# UnderWaterMetalDetector_v2.net
KiCad netlist of a schematic drawn in EAGLE
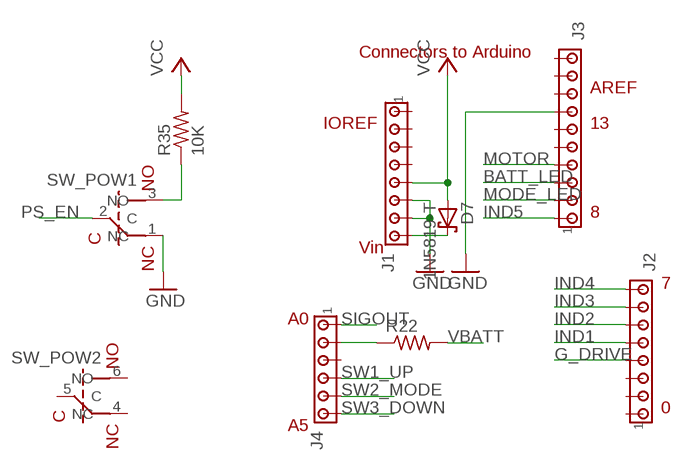
[diagram p0: schematic, sheet 1]
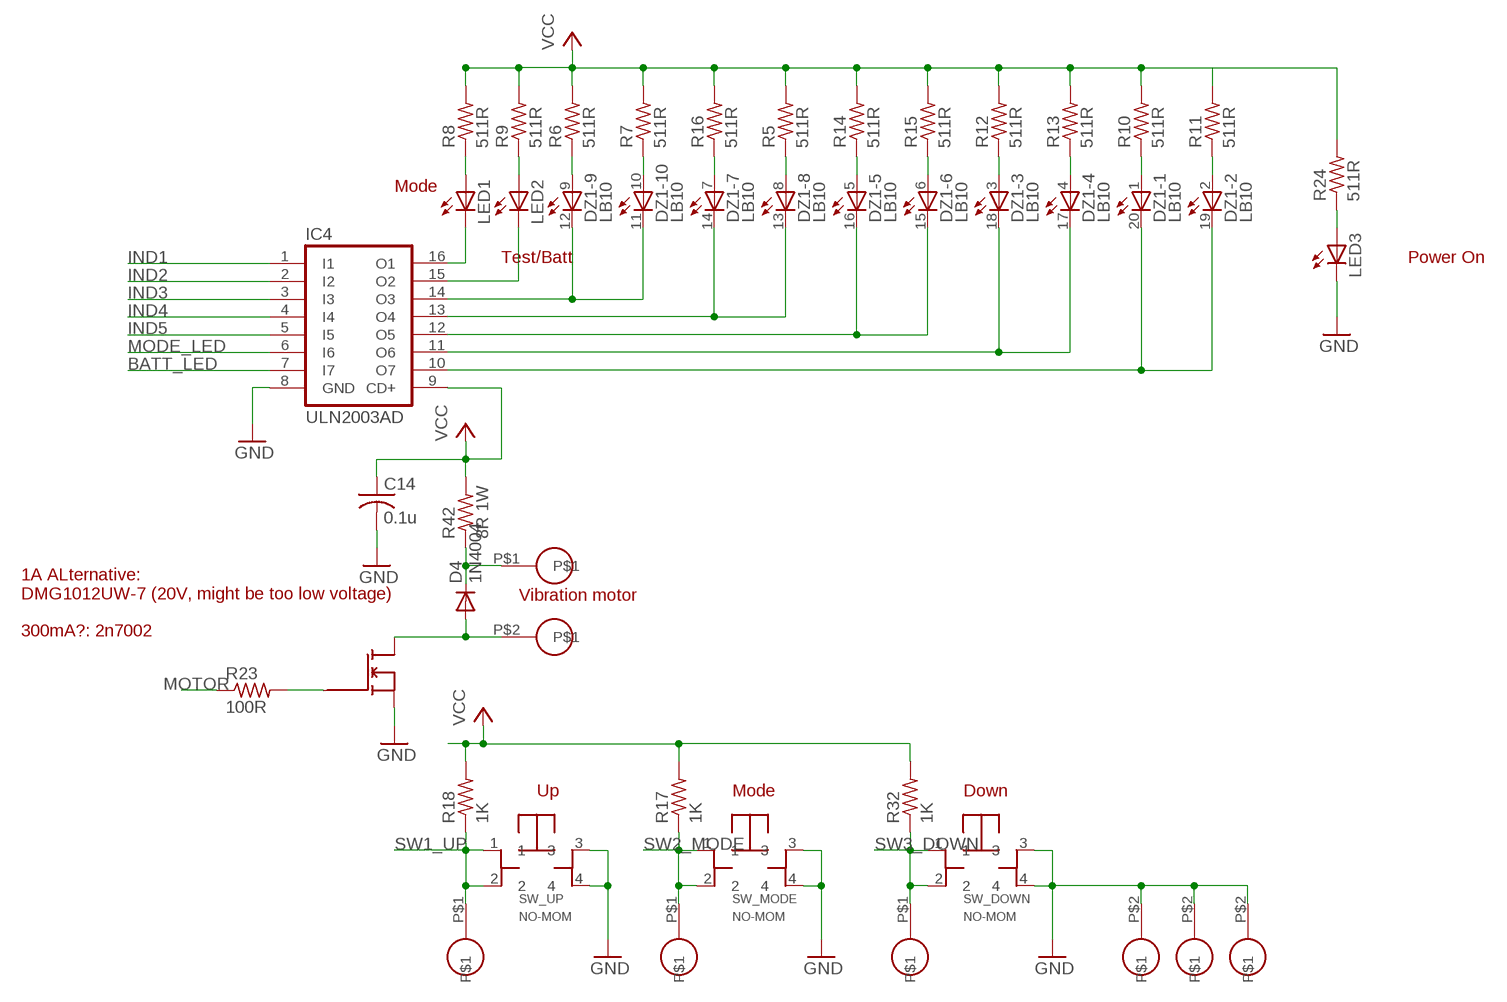
[diagram p1: schematic, sheet 2]
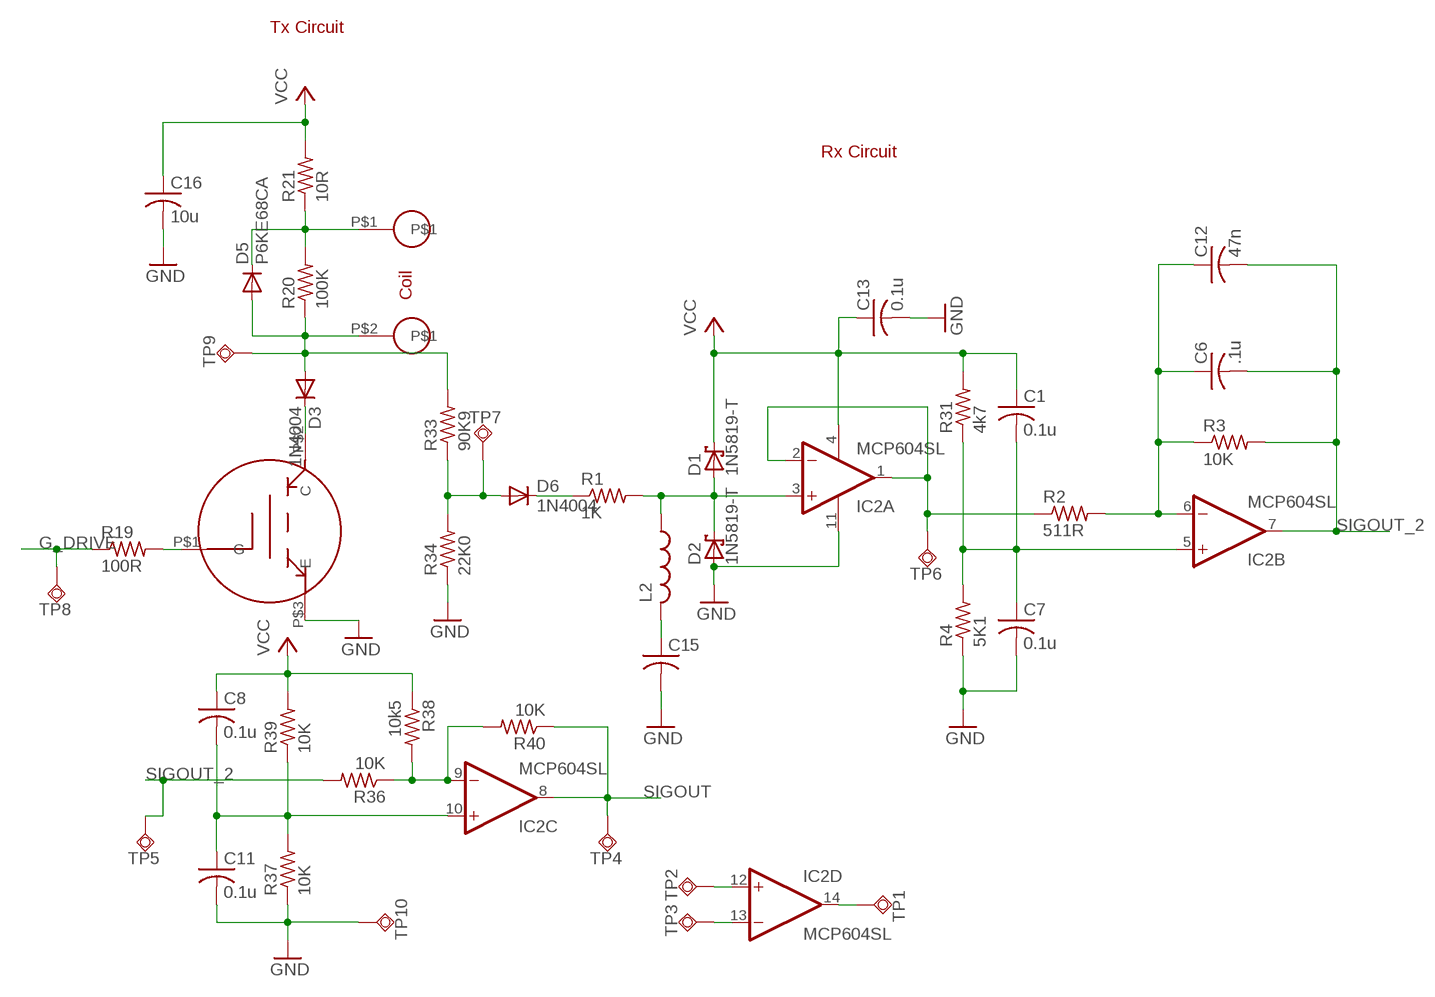
[diagram p2: schematic, sheet 3]
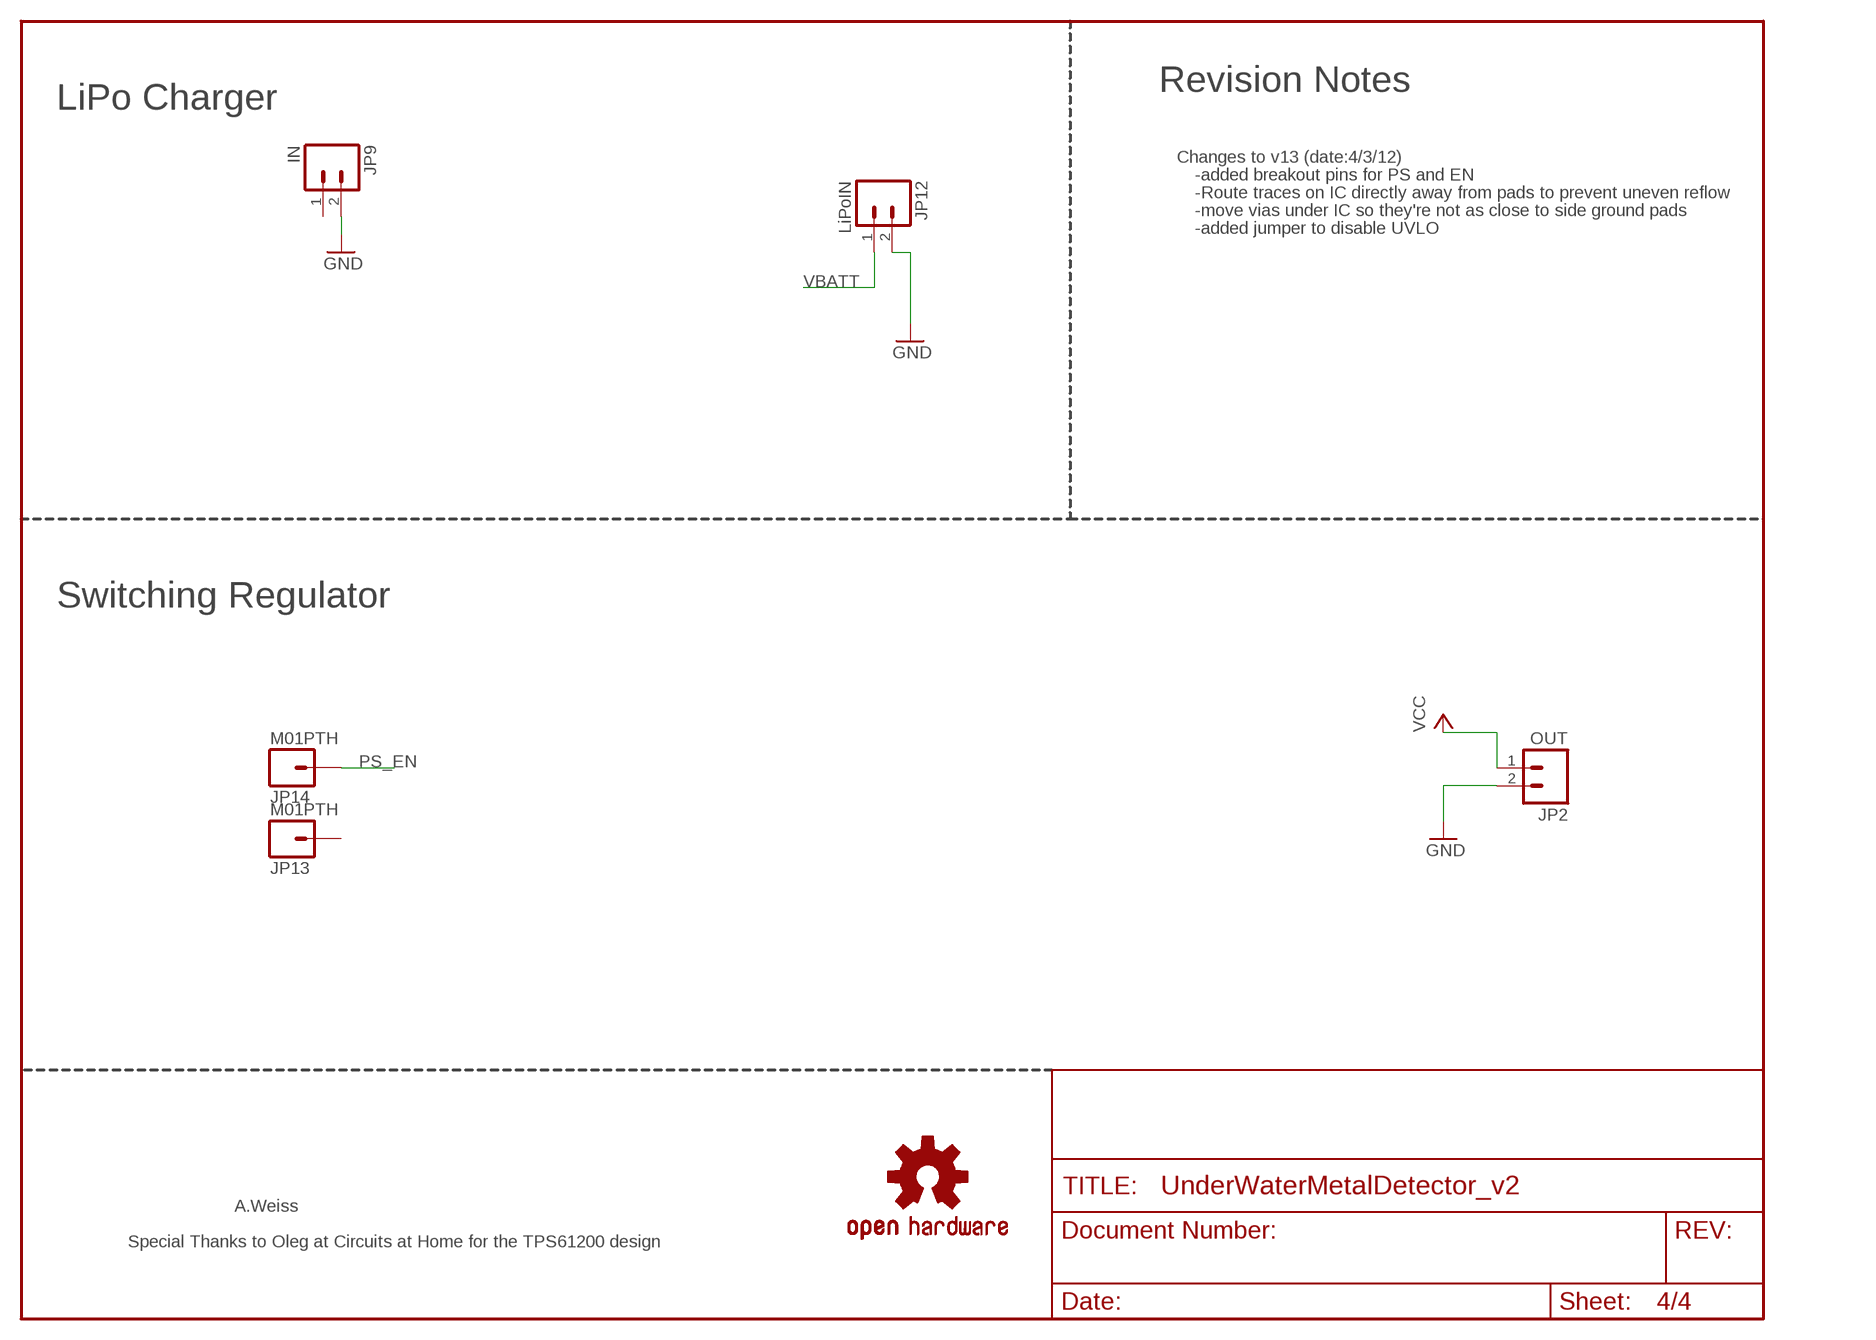
[diagram p3: schematic, sheet 4]

(export (version "E")
  (design (tool "Eeschema 10.0.6"))
  (components
    (comp (ref "C1")
      (value "0.1u")
      (footprint "eagle-import:C1206")
      (libsource (lib "eagle-import") (part "C-USC1206"))
    )
    (comp (ref "C6")
      (value ".1u")
      (footprint "eagle-import:C1206")
      (libsource (lib "eagle-import") (part "C-USC1206"))
    )
    (comp (ref "C7")
      (value "0.1u")
      (footprint "eagle-import:C1206")
      (libsource (lib "eagle-import") (part "C-USC1206"))
    )
    (comp (ref "C8")
      (value "0.1u")
      (footprint "eagle-import:C1206")
      (libsource (lib "eagle-import") (part "C-USC1206"))
    )
    (comp (ref "C11")
      (value "0.1u")
      (footprint "eagle-import:C1206")
      (libsource (lib "eagle-import") (part "C-USC1206"))
    )
    (comp (ref "C12")
      (value "47n")
      (footprint "eagle-import:C1206")
      (libsource (lib "eagle-import") (part "C-USC1206"))
    )
    (comp (ref "C13")
      (value "0.1u")
      (footprint "eagle-import:C1206")
      (libsource (lib "eagle-import") (part "C-USC1206"))
    )
    (comp (ref "C15")
      (value "C-USC1206")
      (footprint "eagle-import:C1206")
      (libsource (lib "eagle-import") (part "C-USC1206"))
    )
    (comp (ref "C16")
      (value "10u")
      (footprint "eagle-import:C1206")
      (libsource (lib "eagle-import") (part "C-USC1206"))
    )
    (comp (ref "COIL")
      (value "CON-SIP2-0.1")
      (footprint "eagle-import:CON-SIP2-0.1")
      (libsource (lib "eagle-import") (part "CON-SIP2-0.1"))
    )
    (comp (ref "D1")
      (value "1N5819-T")
      (footprint "eagle-import:DO41-7.6")
      (libsource (lib "eagle-import") (part "1N5819-T"))
    )
    (comp (ref "D2")
      (value "1N5819-T")
      (footprint "eagle-import:DO41-7.6")
      (libsource (lib "eagle-import") (part "1N5819-T"))
    )
    (comp (ref "D3")
      (value "1N4004")
      (footprint "eagle-import:DO41-10")
      (libsource (lib "eagle-import") (part "1N4004"))
    )
    (comp (ref "D5")
      (value "P6KE68CA")
      (footprint "eagle-import:D-5")
      (libsource (lib "eagle-import") (part "DIODE-D-5"))
    )
    (comp (ref "D6")
      (value "1N4004")
      (footprint "eagle-import:DO41-10")
      (libsource (lib "eagle-import") (part "1N4004"))
    )
    (comp (ref "IC2")
      (value "MCP604SL")
      (footprint "eagle-import:SO14")
      (libsource (lib "eagle-import") (part "MCP604SL"))
    )
    (comp (ref "L2")
      (value "L-US0204V")
      (footprint "eagle-import:0204V")
      (libsource (lib "eagle-import") (part "L-US0204V"))
    )
    (comp (ref "Q1")
      (value "STGP18N40LZ")
      (footprint "eagle-import:TO-220-HORIZ")
      (libsource (lib "eagle-import") (part "STGP18N40LZ"))
    )
    (comp (ref "R1")
      (value "1K")
      (footprint "eagle-import:M1206")
      (libsource (lib "eagle-import") (part "R-US_M1206"))
    )
    (comp (ref "R2")
      (value "511R")
      (footprint "eagle-import:R1206")
      (libsource (lib "eagle-import") (part "R-US_R1206"))
    )
    (comp (ref "R3")
      (value "10K")
      (footprint "eagle-import:R1206")
      (libsource (lib "eagle-import") (part "R-US_R1206"))
    )
    (comp (ref "R4")
      (value "5K1")
      (footprint "eagle-import:R1206")
      (libsource (lib "eagle-import") (part "R-US_R1206"))
    )
    (comp (ref "R19")
      (value "100R")
      (footprint "eagle-import:R1206")
      (libsource (lib "eagle-import") (part "R-US_R1206"))
    )
    (comp (ref "R20")
      (value "100K")
      (footprint "eagle-import:M1206")
      (libsource (lib "eagle-import") (part "R-US_M1206"))
    )
    (comp (ref "R21")
      (value "10R")
      (footprint "eagle-import:R2512")
      (libsource (lib "eagle-import") (part "R-US_R2512"))
    )
    (comp (ref "R31")
      (value "4k7")
      (footprint "eagle-import:R1206")
      (libsource (lib "eagle-import") (part "R-US_R1206"))
    )
    (comp (ref "R33")
      (value "90K9")
      (footprint "eagle-import:M1206")
      (libsource (lib "eagle-import") (part "R-US_M1206"))
    )
    (comp (ref "R34")
      (value "22K0")
      (footprint "eagle-import:M1206")
      (libsource (lib "eagle-import") (part "R-US_M1206"))
    )
    (comp (ref "R36")
      (value "10K")
      (footprint "eagle-import:M1206")
      (libsource (lib "eagle-import") (part "R-US_M1206"))
    )
    (comp (ref "R37")
      (value "10K")
      (footprint "eagle-import:M1206")
      (libsource (lib "eagle-import") (part "R-US_M1206"))
    )
    (comp (ref "R38")
      (value "10k5")
      (footprint "eagle-import:M1206")
      (libsource (lib "eagle-import") (part "R-US_M1206"))
    )
    (comp (ref "R39")
      (value "10K")
      (footprint "eagle-import:M1206")
      (libsource (lib "eagle-import") (part "R-US_M1206"))
    )
    (comp (ref "R40")
      (value "10K")
      (footprint "eagle-import:M1206")
      (libsource (lib "eagle-import") (part "R-US_M1206"))
    )
    (comp (ref "TP1")
      (value "TPSQPAD1-13")
      (footprint "eagle-import:P1-13")
      (libsource (lib "eagle-import") (part "TPSQPAD1-13"))
    )
    (comp (ref "TP2")
      (value "TPSQPAD1-13")
      (footprint "eagle-import:P1-13")
      (libsource (lib "eagle-import") (part "TPSQPAD1-13"))
    )
    (comp (ref "TP3")
      (value "TPSQPAD1-13")
      (footprint "eagle-import:P1-13")
      (libsource (lib "eagle-import") (part "TPSQPAD1-13"))
    )
    (comp (ref "TP4")
      (value "TPSQPAD1-13")
      (footprint "eagle-import:P1-13")
      (libsource (lib "eagle-import") (part "TPSQPAD1-13"))
    )
    (comp (ref "TP5")
      (value "TPSQPAD1-13")
      (footprint "eagle-import:P1-13")
      (libsource (lib "eagle-import") (part "TPSQPAD1-13"))
    )
    (comp (ref "TP6")
      (value "TPSQPAD1-13")
      (footprint "eagle-import:P1-13")
      (libsource (lib "eagle-import") (part "TPSQPAD1-13"))
    )
    (comp (ref "TP7")
      (value "TPSQPAD1-13")
      (footprint "eagle-import:P1-13")
      (libsource (lib "eagle-import") (part "TPSQPAD1-13"))
    )
    (comp (ref "TP8")
      (value "TPSQPAD1-13")
      (footprint "eagle-import:P1-13")
      (libsource (lib "eagle-import") (part "TPSQPAD1-13"))
    )
    (comp (ref "TP9")
      (value "TPSQPAD1-13")
      (footprint "eagle-import:P1-13")
      (libsource (lib "eagle-import") (part "TPSQPAD1-13"))
    )
    (comp (ref "TP10")
      (value "TPSQPAD1-13")
      (footprint "eagle-import:P1-13")
      (libsource (lib "eagle-import") (part "TPSQPAD1-13"))
    )
    (comp (ref "D7")
      (value "1N5819-T")
      (footprint "eagle-import:DO41-7.6")
      (libsource (lib "eagle-import") (part "1N5819-T"))
    )
    (comp (ref "J1")
      (value "MTA08-100")
      (footprint "eagle-import:10X08MTA")
      (libsource (lib "eagle-import") (part "MTA08-100"))
    )
    (comp (ref "J2")
      (value "MTA08-100")
      (footprint "eagle-import:10X08MTA")
      (libsource (lib "eagle-import") (part "MTA08-100"))
    )
    (comp (ref "J3")
      (value "MTA10-100")
      (footprint "eagle-import:10X10MTA")
      (libsource (lib "eagle-import") (part "MTA10-100"))
    )
    (comp (ref "J4")
      (value "MTA06-100")
      (footprint "eagle-import:10X06MTA")
      (libsource (lib "eagle-import") (part "MTA06-100"))
    )
    (comp (ref "R22")
      (value "R-US_R1206")
      (footprint "eagle-import:R1206")
      (libsource (lib "eagle-import") (part "R-US_R1206"))
    )
    (comp (ref "R35")
      (value "10K")
      (footprint "eagle-import:R1206")
      (libsource (lib "eagle-import") (part "R-US_R1206"))
    )
    (comp (ref "SW_POW")
      (value "SW-TL2201EEYA")
      (footprint "eagle-import:SW-TL2201EEYA")
      (libsource (lib "eagle-import") (part "SW-TL2201EEYA"))
    )
    (comp (ref "C14")
      (value "0.1u")
      (footprint "eagle-import:C1206")
      (libsource (lib "eagle-import") (part "C-USC1206"))
    )
    (comp (ref "D4")
      (value "1N4004")
      (footprint "eagle-import:DO41-10")
      (libsource (lib "eagle-import") (part "1N4004"))
    )
    (comp (ref "DOWN")
      (value "CON-SIP2-0.1")
      (footprint "eagle-import:CON-SIP2-0.1")
      (libsource (lib "eagle-import") (part "CON-SIP2-0.1"))
    )
    (comp (ref "DZ1")
      (value "LB10")
      (footprint "eagle-import:LB10")
      (libsource (lib "eagle-import") (part "LB10"))
    )
    (comp (ref "IC4")
      (value "ULN2003AD")
      (footprint "eagle-import:SO16")
      (libsource (lib "eagle-import") (part "ULN2003AD"))
    )
    (comp (ref "LED1")
      (value "LED5MM")
      (footprint "eagle-import:LED5MM")
      (libsource (lib "eagle-import") (part "LED5MM"))
    )
    (comp (ref "LED2")
      (value "LED5MM")
      (footprint "eagle-import:LED5MM")
      (libsource (lib "eagle-import") (part "LED5MM"))
    )
    (comp (ref "LED3")
      (value "LED5MM")
      (footprint "eagle-import:LED5MM")
      (libsource (lib "eagle-import") (part "LED5MM"))
    )
    (comp (ref "MODE")
      (value "CON-SIP2-0.1")
      (footprint "eagle-import:CON-SIP2-0.1")
      (libsource (lib "eagle-import") (part "CON-SIP2-0.1"))
    )
    (comp (ref "MOTOR")
      (value "CON-SIP2-0.1")
      (footprint "eagle-import:CON-SIP2-0.1")
      (libsource (lib "eagle-import") (part "CON-SIP2-0.1"))
    )
    (comp (ref "Q2")
      (value "FET-2N7000")
      (footprint "eagle-import:TO92")
      (libsource (lib "eagle-import") (part "FET-2N7000"))
    )
    (comp (ref "R5")
      (value "511R")
      (footprint "eagle-import:M1206")
      (libsource (lib "eagle-import") (part "R-US_M1206"))
    )
    (comp (ref "R6")
      (value "511R")
      (footprint "eagle-import:M1206")
      (libsource (lib "eagle-import") (part "R-US_M1206"))
    )
    (comp (ref "R7")
      (value "511R")
      (footprint "eagle-import:M1206")
      (libsource (lib "eagle-import") (part "R-US_M1206"))
    )
    (comp (ref "R8")
      (value "511R")
      (footprint "eagle-import:M1206")
      (libsource (lib "eagle-import") (part "R-US_M1206"))
    )
    (comp (ref "R9")
      (value "511R")
      (footprint "eagle-import:M1206")
      (libsource (lib "eagle-import") (part "R-US_M1206"))
    )
    (comp (ref "R10")
      (value "511R")
      (footprint "eagle-import:M1206")
      (libsource (lib "eagle-import") (part "R-US_M1206"))
    )
    (comp (ref "R11")
      (value "511R")
      (footprint "eagle-import:M1206")
      (libsource (lib "eagle-import") (part "R-US_M1206"))
    )
    (comp (ref "R12")
      (value "511R")
      (footprint "eagle-import:M1206")
      (libsource (lib "eagle-import") (part "R-US_M1206"))
    )
    (comp (ref "R13")
      (value "511R")
      (footprint "eagle-import:M1206")
      (libsource (lib "eagle-import") (part "R-US_M1206"))
    )
    (comp (ref "R14")
      (value "511R")
      (footprint "eagle-import:M1206")
      (libsource (lib "eagle-import") (part "R-US_M1206"))
    )
    (comp (ref "R15")
      (value "511R")
      (footprint "eagle-import:M1206")
      (libsource (lib "eagle-import") (part "R-US_M1206"))
    )
    (comp (ref "R16")
      (value "511R")
      (footprint "eagle-import:M1206")
      (libsource (lib "eagle-import") (part "R-US_M1206"))
    )
    (comp (ref "R17")
      (value "1K")
      (footprint "eagle-import:M1206")
      (libsource (lib "eagle-import") (part "R-US_M1206"))
    )
    (comp (ref "R18")
      (value "1K")
      (footprint "eagle-import:M1206")
      (libsource (lib "eagle-import") (part "R-US_M1206"))
    )
    (comp (ref "R23")
      (value "100R")
      (footprint "eagle-import:R1206")
      (libsource (lib "eagle-import") (part "R-US_R1206"))
    )
    (comp (ref "R24")
      (value "511R")
      (footprint "eagle-import:M1206")
      (libsource (lib "eagle-import") (part "R-US_M1206"))
    )
    (comp (ref "R32")
      (value "1K")
      (footprint "eagle-import:M1206")
      (libsource (lib "eagle-import") (part "R-US_M1206"))
    )
    (comp (ref "R42")
      (value "8R 1W")
      (footprint "eagle-import:R2512")
      (libsource (lib "eagle-import") (part "R-US_R2512"))
    )
    (comp (ref "SW_DOWN")
      (value "SW-SCHURTER-1301.9306")
      (footprint "eagle-import:SW-SCHURTER-1301.9306")
      (libsource (lib "eagle-import") (part "SW-SCHURTER-1301.9306"))
    )
    (comp (ref "SW_MODE")
      (value "SW-SCHURTER-1301.9306")
      (footprint "eagle-import:SW-SCHURTER-1301.9306")
      (libsource (lib "eagle-import") (part "SW-SCHURTER-1301.9306"))
    )
    (comp (ref "SW_UP")
      (value "SW-SCHURTER-1301.9306")
      (footprint "eagle-import:SW-SCHURTER-1301.9306")
      (libsource (lib "eagle-import") (part "SW-SCHURTER-1301.9306"))
    )
    (comp (ref "UP")
      (value "CON-SIP2-0.1")
      (footprint "eagle-import:CON-SIP2-0.1")
      (libsource (lib "eagle-import") (part "CON-SIP2-0.1"))
    )
    (comp (ref "JP2")
      (value "OUT")
      (footprint "eagle-import:1X02")
      (libsource (lib "eagle-import") (part "M02PTH"))
    )
    (comp (ref "JP9")
      (value "IN")
      (footprint "eagle-import:1X02")
      (libsource (lib "eagle-import") (part "M02PTH"))
    )
    (comp (ref "JP12")
      (value "LiPoIN")
      (footprint "eagle-import:1X02")
      (libsource (lib "eagle-import") (part "M02PTH"))
    )
    (comp (ref "JP13")
      (value "M01PTH")
      (footprint "eagle-import:1X01")
      (libsource (lib "eagle-import") (part "M01PTH"))
    )
    (comp (ref "JP14")
      (value "M01PTH")
      (footprint "eagle-import:1X01")
      (libsource (lib "eagle-import") (part "M01PTH"))
    )
    (comp (ref "U$3")
      (value "OSHW-LOGOS")
      (footprint "eagle-import:OSHW-LOGO-S")
      (libsource (lib "eagle-import") (part "OSHW-LOGOS"))
    )
  )
  (nets
    (net (code "1") (name "BATT_LED") (class "Default")
      (node (ref "IC4") (pin "7") (pinfunction "I7_7") (pintype "input"))
      (node (ref "J3") (pin "3") (pinfunction "3_3") (pintype "passive"))
    )
    (net (code "2") (name "GND") (class "Default")
      (node (ref "C11") (pin "2") (pinfunction "2_2") (pintype "passive"))
      (node (ref "C13") (pin "2") (pinfunction "2_2") (pintype "passive"))
      (node (ref "C14") (pin "2") (pinfunction "2_2") (pintype "passive"))
      (node (ref "C15") (pin "2") (pinfunction "2_2") (pintype "passive"))
      (node (ref "C16") (pin "2") (pinfunction "2_2") (pintype "passive"))
      (node (ref "C7") (pin "2") (pinfunction "2_2") (pintype "passive"))
      (node (ref "D2") (pin "A") (pinfunction "A_A") (pintype "passive"))
      (node (ref "DOWN") (pin "P$2") (pinfunction "P$1_P$2") (pintype "bidirectional"))
      (node (ref "IC2") (pin "11") (pinfunction "V-_11") (pintype "power_in"))
      (node (ref "IC4") (pin "8") (pinfunction "GND_8") (pintype "power_in"))
      (node (ref "J1") (pin "6") (pinfunction "6_6") (pintype "passive"))
      (node (ref "J1") (pin "7") (pinfunction "7_7") (pintype "passive"))
      (node (ref "J3") (pin "7") (pinfunction "7_7") (pintype "passive"))
      (node (ref "JP12") (pin "2") (pinfunction "2_2") (pintype "passive"))
      (node (ref "JP2") (pin "2") (pinfunction "2_2") (pintype "passive"))
      (node (ref "JP9") (pin "2") (pinfunction "2_2") (pintype "passive"))
      (node (ref "LED3") (pin "K") (pinfunction "C_K") (pintype "passive"))
      (node (ref "MODE") (pin "P$2") (pinfunction "P$1_P$2") (pintype "bidirectional"))
      (node (ref "Q1") (pin "P$3") (pinfunction "E_P$3") (pintype "bidirectional"))
      (node (ref "Q2") (pin "1") (pinfunction "S_1") (pintype "bidirectional"))
      (node (ref "R34") (pin "1") (pinfunction "1_1") (pintype "passive"))
      (node (ref "R37") (pin "1") (pinfunction "1_1") (pintype "passive"))
      (node (ref "R4") (pin "1") (pinfunction "1_1") (pintype "passive"))
      (node (ref "SW_DOWN") (pin "3") (pinfunction "3_3") (pintype "bidirectional"))
      (node (ref "SW_DOWN") (pin "4") (pinfunction "4_4") (pintype "bidirectional"))
      (node (ref "SW_MODE") (pin "3") (pinfunction "3_3") (pintype "bidirectional"))
      (node (ref "SW_MODE") (pin "4") (pinfunction "4_4") (pintype "bidirectional"))
      (node (ref "SW_POW") (pin "1") (pinfunction "NC_1") (pintype "bidirectional"))
      (node (ref "SW_UP") (pin "3") (pinfunction "3_3") (pintype "bidirectional"))
      (node (ref "SW_UP") (pin "4") (pinfunction "4_4") (pintype "bidirectional"))
      (node (ref "TP10") (pin "TP") (pinfunction "TP_TP") (pintype "input"))
      (node (ref "UP") (pin "P$2") (pinfunction "P$1_P$2") (pintype "bidirectional"))
    )
    (net (code "3") (name "G_DRIVE") (class "Default")
      (node (ref "J2") (pin "4") (pinfunction "4_4") (pintype "passive"))
      (node (ref "R19") (pin "1") (pinfunction "1_1") (pintype "passive"))
      (node (ref "TP8") (pin "TP") (pinfunction "TP_TP") (pintype "input"))
    )
    (net (code "4") (name "IND1") (class "Default")
      (node (ref "IC4") (pin "1") (pinfunction "I1_1") (pintype "input"))
      (node (ref "J2") (pin "5") (pinfunction "5_5") (pintype "passive"))
    )
    (net (code "5") (name "IND2") (class "Default")
      (node (ref "IC4") (pin "2") (pinfunction "I2_2") (pintype "input"))
      (node (ref "J2") (pin "6") (pinfunction "6_6") (pintype "passive"))
    )
    (net (code "6") (name "IND3") (class "Default")
      (node (ref "IC4") (pin "3") (pinfunction "I3_3") (pintype "input"))
      (node (ref "J2") (pin "7") (pinfunction "7_7") (pintype "passive"))
    )
    (net (code "7") (name "IND4") (class "Default")
      (node (ref "IC4") (pin "4") (pinfunction "I4_4") (pintype "input"))
      (node (ref "J2") (pin "8") (pinfunction "8_8") (pintype "passive"))
    )
    (net (code "8") (name "IND5") (class "Default")
      (node (ref "IC4") (pin "5") (pinfunction "I5_5") (pintype "input"))
      (node (ref "J3") (pin "1") (pinfunction "1_1") (pintype "passive"))
    )
    (net (code "9") (name "MODE_LED") (class "Default")
      (node (ref "IC4") (pin "6") (pinfunction "I6_6") (pintype "input"))
      (node (ref "J3") (pin "2") (pinfunction "2_2") (pintype "passive"))
    )
    (net (code "10") (name "MOTOR") (class "Default")
      (node (ref "J3") (pin "4") (pinfunction "4_4") (pintype "passive"))
      (node (ref "R23") (pin "1") (pinfunction "1_1") (pintype "passive"))
    )
    (net (code "11") (name "Net-(C15-Pad1)") (class "Default")
      (node (ref "C15") (pin "1") (pinfunction "1_1") (pintype "passive"))
      (node (ref "L2") (pin "2") (pinfunction "2_2") (pintype "passive"))
    )
    (net (code "12") (name "Net-(COIL-PadP$1)") (class "Default")
      (node (ref "COIL") (pin "P$1") (pinfunction "P$1_P$1") (pintype "bidirectional"))
      (node (ref "D5") (pin "C") (pinfunction "C_C") (pintype "passive"))
      (node (ref "R20") (pin "2") (pinfunction "2_2") (pintype "passive"))
      (node (ref "R21") (pin "1") (pinfunction "1_1") (pintype "passive"))
    )
    (net (code "13") (name "Net-(COILB-P$1)") (class "Default")
      (node (ref "COIL") (pin "P$2") (pinfunction "P$1_P$2") (pintype "bidirectional"))
      (node (ref "D3") (pin "A") (pinfunction "A_A") (pintype "passive"))
      (node (ref "D5") (pin "A") (pinfunction "A_A") (pintype "passive"))
      (node (ref "R20") (pin "1") (pinfunction "1_1") (pintype "passive"))
      (node (ref "R33") (pin "2") (pinfunction "2_2") (pintype "passive"))
      (node (ref "TP9") (pin "TP") (pinfunction "TP_TP") (pintype "input"))
    )
    (net (code "14") (name "Net-(D4-PadC)") (class "Default")
      (node (ref "D4") (pin "C") (pinfunction "C_C") (pintype "passive"))
      (node (ref "MOTOR") (pin "P$1") (pinfunction "P$1_P$1") (pintype "bidirectional"))
      (node (ref "R42") (pin "1") (pinfunction "1_1") (pintype "passive"))
    )
    (net (code "15") (name "Net-(D6-PadA)") (class "Default")
      (node (ref "D6") (pin "A") (pinfunction "A_A") (pintype "passive"))
      (node (ref "R33") (pin "1") (pinfunction "1_1") (pintype "passive"))
      (node (ref "R34") (pin "2") (pinfunction "2_2") (pintype "passive"))
      (node (ref "TP7") (pin "TP") (pinfunction "TP_TP") (pintype "input"))
    )
    (net (code "16") (name "Net-(D6-PadC)") (class "Default")
      (node (ref "D6") (pin "C") (pinfunction "C_C") (pintype "passive"))
      (node (ref "R1") (pin "1") (pinfunction "1_1") (pintype "passive"))
    )
    (net (code "17") (name "Net-(D7-PadC)") (class "Default")
      (node (ref "D7") (pin "C") (pinfunction "C_C") (pintype "passive"))
      (node (ref "J1") (pin "8") (pinfunction "8_8") (pintype "passive"))
    )
    (net (code "18") (name "Net-(DZ1A-A)") (class "Default")
      (node (ref "DZ1") (pin "1") (pinfunction "A_1") (pintype "passive"))
      (node (ref "R10") (pin "1") (pinfunction "1_1") (pintype "passive"))
    )
    (net (code "19") (name "Net-(DZ1A-C)") (class "Default")
      (node (ref "DZ1") (pin "19") (pinfunction "C_19") (pintype "passive"))
      (node (ref "DZ1") (pin "20") (pinfunction "C_20") (pintype "passive"))
      (node (ref "IC4") (pin "10") (pinfunction "O7_10") (pintype "open_collector"))
    )
    (net (code "20") (name "Net-(DZ1B-A)") (class "Default")
      (node (ref "DZ1") (pin "10") (pinfunction "A_10") (pintype "passive"))
      (node (ref "R7") (pin "1") (pinfunction "1_1") (pintype "passive"))
    )
    (net (code "21") (name "Net-(DZ1B-C)") (class "Default")
      (node (ref "DZ1") (pin "11") (pinfunction "C_11") (pintype "passive"))
      (node (ref "DZ1") (pin "12") (pinfunction "C_12") (pintype "passive"))
      (node (ref "IC4") (pin "14") (pinfunction "O3_14") (pintype "open_collector"))
    )
    (net (code "22") (name "Net-(DZ1C-A)") (class "Default")
      (node (ref "DZ1") (pin "2") (pinfunction "A_2") (pintype "passive"))
      (node (ref "R11") (pin "1") (pinfunction "1_1") (pintype "passive"))
    )
    (net (code "23") (name "Net-(DZ1D-A)") (class "Default")
      (node (ref "DZ1") (pin "3") (pinfunction "A_3") (pintype "passive"))
      (node (ref "R12") (pin "1") (pinfunction "1_1") (pintype "passive"))
    )
    (net (code "24") (name "Net-(DZ1D-C)") (class "Default")
      (node (ref "DZ1") (pin "17") (pinfunction "C_17") (pintype "passive"))
      (node (ref "DZ1") (pin "18") (pinfunction "C_18") (pintype "passive"))
      (node (ref "IC4") (pin "11") (pinfunction "O6_11") (pintype "open_collector"))
    )
    (net (code "25") (name "Net-(DZ1E-A)") (class "Default")
      (node (ref "DZ1") (pin "4") (pinfunction "A_4") (pintype "passive"))
      (node (ref "R13") (pin "1") (pinfunction "1_1") (pintype "passive"))
    )
    (net (code "26") (name "Net-(DZ1F-A)") (class "Default")
      (node (ref "DZ1") (pin "5") (pinfunction "A_5") (pintype "passive"))
      (node (ref "R14") (pin "1") (pinfunction "1_1") (pintype "passive"))
    )
    (net (code "27") (name "Net-(DZ1F-C)") (class "Default")
      (node (ref "DZ1") (pin "15") (pinfunction "C_15") (pintype "passive"))
      (node (ref "DZ1") (pin "16") (pinfunction "C_16") (pintype "passive"))
      (node (ref "IC4") (pin "12") (pinfunction "O5_12") (pintype "open_collector"))
    )
    (net (code "28") (name "Net-(DZ1G-A)") (class "Default")
      (node (ref "DZ1") (pin "6") (pinfunction "A_6") (pintype "passive"))
      (node (ref "R15") (pin "1") (pinfunction "1_1") (pintype "passive"))
    )
    (net (code "29") (name "Net-(DZ1H-A)") (class "Default")
      (node (ref "DZ1") (pin "7") (pinfunction "A_7") (pintype "passive"))
      (node (ref "R16") (pin "1") (pinfunction "1_1") (pintype "passive"))
    )
    (net (code "30") (name "Net-(DZ1H-C)") (class "Default")
      (node (ref "DZ1") (pin "13") (pinfunction "C_13") (pintype "passive"))
      (node (ref "DZ1") (pin "14") (pinfunction "C_14") (pintype "passive"))
      (node (ref "IC4") (pin "13") (pinfunction "O4_13") (pintype "open_collector"))
    )
    (net (code "31") (name "Net-(DZ1I-A)") (class "Default")
      (node (ref "DZ1") (pin "8") (pinfunction "A_8") (pintype "passive"))
      (node (ref "R5") (pin "1") (pinfunction "1_1") (pintype "passive"))
    )
    (net (code "32") (name "Net-(DZ1J-A)") (class "Default")
      (node (ref "DZ1") (pin "9") (pinfunction "A_9") (pintype "passive"))
      (node (ref "R6") (pin "1") (pinfunction "1_1") (pintype "passive"))
    )
    (net (code "33") (name "Net-(IC2A-+IN)") (class "Default")
      (node (ref "D1") (pin "A") (pinfunction "A_A") (pintype "passive"))
      (node (ref "D2") (pin "C") (pinfunction "C_C") (pintype "passive"))
      (node (ref "IC2") (pin "3") (pinfunction "+IN_3") (pintype "input"))
      (node (ref "L2") (pin "1") (pinfunction "1_1") (pintype "passive"))
      (node (ref "R1") (pin "2") (pinfunction "2_2") (pintype "passive"))
    )
    (net (code "34") (name "Net-(IC2A--IN)") (class "Default")
      (node (ref "IC2") (pin "1") (pinfunction "OUT_1") (pintype "output"))
      (node (ref "IC2") (pin "2") (pinfunction "-IN_2") (pintype "input"))
      (node (ref "R2") (pin "1") (pinfunction "1_1") (pintype "passive"))
      (node (ref "TP6") (pin "TP") (pinfunction "TP_TP") (pintype "input"))
    )
    (net (code "35") (name "Net-(IC2B-+IN)") (class "Default")
      (node (ref "C1") (pin "2") (pinfunction "2_2") (pintype "passive"))
      (node (ref "C7") (pin "1") (pinfunction "1_1") (pintype "passive"))
      (node (ref "IC2") (pin "5") (pinfunction "+IN_5") (pintype "input"))
      (node (ref "R31") (pin "1") (pinfunction "1_1") (pintype "passive"))
      (node (ref "R4") (pin "2") (pinfunction "2_2") (pintype "passive"))
    )
    (net (code "36") (name "Net-(IC2B--IN)") (class "Default")
      (node (ref "C12") (pin "1") (pinfunction "1_1") (pintype "passive"))
      (node (ref "C6") (pin "1") (pinfunction "1_1") (pintype "passive"))
      (node (ref "IC2") (pin "6") (pinfunction "-IN_6") (pintype "input"))
      (node (ref "R2") (pin "2") (pinfunction "2_2") (pintype "passive"))
      (node (ref "R3") (pin "1") (pinfunction "1_1") (pintype "passive"))
    )
    (net (code "37") (name "Net-(IC2C-+IN)") (class "Default")
      (node (ref "C11") (pin "1") (pinfunction "1_1") (pintype "passive"))
      (node (ref "C8") (pin "2") (pinfunction "2_2") (pintype "passive"))
      (node (ref "IC2") (pin "10") (pinfunction "+IN_10") (pintype "input"))
      (node (ref "R37") (pin "2") (pinfunction "2_2") (pintype "passive"))
      (node (ref "R39") (pin "1") (pinfunction "1_1") (pintype "passive"))
    )
    (net (code "38") (name "Net-(IC2C--IN)") (class "Default")
      (node (ref "IC2") (pin "9") (pinfunction "-IN_9") (pintype "input"))
      (node (ref "R36") (pin "1") (pinfunction "1_1") (pintype "passive"))
      (node (ref "R38") (pin "2") (pinfunction "2_2") (pintype "passive"))
      (node (ref "R40") (pin "2") (pinfunction "2_2") (pintype "passive"))
    )
    (net (code "39") (name "Net-(IC2D-+IN)") (class "Default")
      (node (ref "IC2") (pin "12") (pinfunction "+IN_12") (pintype "input"))
      (node (ref "TP2") (pin "TP") (pinfunction "TP_TP") (pintype "input"))
    )
    (net (code "40") (name "Net-(IC2D--IN)") (class "Default")
      (node (ref "IC2") (pin "13") (pinfunction "-IN_13") (pintype "input"))
      (node (ref "TP3") (pin "TP") (pinfunction "TP_TP") (pintype "input"))
    )
    (net (code "41") (name "Net-(IC2D-OUT)") (class "Default")
      (node (ref "IC2") (pin "14") (pinfunction "OUT_14") (pintype "output"))
      (node (ref "TP1") (pin "TP") (pinfunction "TP_TP") (pintype "input"))
    )
    (net (code "42") (name "Net-(IC4-O1)") (class "Default")
      (node (ref "IC4") (pin "16") (pinfunction "O1_16") (pintype "open_collector"))
      (node (ref "LED1") (pin "K") (pinfunction "C_K") (pintype "passive"))
    )
    (net (code "43") (name "Net-(IC4-O2)") (class "Default")
      (node (ref "IC4") (pin "15") (pinfunction "O2_15") (pintype "open_collector"))
      (node (ref "LED2") (pin "K") (pinfunction "C_K") (pintype "passive"))
    )
    (net (code "44") (name "Net-(J4-2)") (class "Default")
      (node (ref "J4") (pin "5") (pinfunction "2_5") (pintype "passive"))
      (node (ref "R22") (pin "1") (pinfunction "1_1") (pintype "passive"))
    )
    (net (code "45") (name "Net-(LED1-PadA)") (class "Default")
      (node (ref "LED1") (pin "A") (pinfunction "A_A") (pintype "passive"))
      (node (ref "R8") (pin "1") (pinfunction "1_1") (pintype "passive"))
    )
    (net (code "46") (name "Net-(LED2-PadA)") (class "Default")
      (node (ref "LED2") (pin "A") (pinfunction "A_A") (pintype "passive"))
      (node (ref "R9") (pin "1") (pinfunction "1_1") (pintype "passive"))
    )
    (net (code "47") (name "Net-(LED3-PadA)") (class "Default")
      (node (ref "LED3") (pin "A") (pinfunction "A_A") (pintype "passive"))
      (node (ref "R24") (pin "1") (pinfunction "1_1") (pintype "passive"))
    )
    (net (code "48") (name "Net-(MOTORB-P$1)") (class "Default")
      (node (ref "D4") (pin "A") (pinfunction "A_A") (pintype "passive"))
      (node (ref "MOTOR") (pin "P$2") (pinfunction "P$1_P$2") (pintype "bidirectional"))
      (node (ref "Q2") (pin "3") (pinfunction "D_3") (pintype "bidirectional"))
    )
    (net (code "49") (name "Net-(Q1-C)") (class "Default")
      (node (ref "D3") (pin "C") (pinfunction "C_C") (pintype "passive"))
      (node (ref "Q1") (pin "P$2") (pinfunction "C_P$2") (pintype "bidirectional"))
    )
    (net (code "50") (name "Net-(Q1-G)") (class "Default")
      (node (ref "Q1") (pin "P$1") (pinfunction "G_P$1") (pintype "bidirectional"))
      (node (ref "R19") (pin "2") (pinfunction "2_2") (pintype "passive"))
    )
    (net (code "51") (name "Net-(Q2-G)") (class "Default")
      (node (ref "Q2") (pin "2") (pinfunction "G_2") (pintype "bidirectional"))
      (node (ref "R23") (pin "2") (pinfunction "2_2") (pintype "passive"))
    )
    (net (code "52") (name "Net-(SW_POWA-NO)") (class "Default")
      (node (ref "R35") (pin "1") (pinfunction "1_1") (pintype "passive"))
      (node (ref "SW_POW") (pin "3") (pinfunction "NO_3") (pintype "bidirectional"))
    )
    (net (code "53") (name "PS_EN") (class "Default")
      (node (ref "JP14") (pin "1") (pinfunction "1_1") (pintype "passive"))
      (node (ref "SW_POW") (pin "2") (pinfunction "C_2") (pintype "bidirectional"))
    )
    (net (code "54") (name "SIGOUT") (class "Default")
      (node (ref "IC2") (pin "8") (pinfunction "OUT_8") (pintype "output"))
      (node (ref "J4") (pin "6") (pinfunction "1_6") (pintype "passive"))
      (node (ref "R40") (pin "1") (pinfunction "1_1") (pintype "passive"))
      (node (ref "TP4") (pin "TP") (pinfunction "TP_TP") (pintype "input"))
    )
    (net (code "55") (name "SIGOUT_2") (class "Default")
      (node (ref "C12") (pin "2") (pinfunction "2_2") (pintype "passive"))
      (node (ref "C6") (pin "2") (pinfunction "2_2") (pintype "passive"))
      (node (ref "IC2") (pin "7") (pinfunction "OUT_7") (pintype "output"))
      (node (ref "R3") (pin "2") (pinfunction "2_2") (pintype "passive"))
      (node (ref "R36") (pin "2") (pinfunction "2_2") (pintype "passive"))
      (node (ref "TP5") (pin "TP") (pinfunction "TP_TP") (pintype "input"))
    )
    (net (code "56") (name "SW1_UP") (class "Default")
      (node (ref "J4") (pin "3") (pinfunction "4_3") (pintype "passive"))
      (node (ref "R18") (pin "1") (pinfunction "1_1") (pintype "passive"))
      (node (ref "SW_UP") (pin "1") (pinfunction "1_1") (pintype "bidirectional"))
      (node (ref "SW_UP") (pin "2") (pinfunction "2_2") (pintype "bidirectional"))
      (node (ref "UP") (pin "P$1") (pinfunction "P$1_P$1") (pintype "bidirectional"))
    )
    (net (code "57") (name "SW2_MODE") (class "Default")
      (node (ref "J4") (pin "2") (pinfunction "5_2") (pintype "passive"))
      (node (ref "MODE") (pin "P$1") (pinfunction "P$1_P$1") (pintype "bidirectional"))
      (node (ref "R17") (pin "1") (pinfunction "1_1") (pintype "passive"))
      (node (ref "SW_MODE") (pin "1") (pinfunction "1_1") (pintype "bidirectional"))
      (node (ref "SW_MODE") (pin "2") (pinfunction "2_2") (pintype "bidirectional"))
    )
    (net (code "58") (name "SW3_DOWN") (class "Default")
      (node (ref "DOWN") (pin "P$1") (pinfunction "P$1_P$1") (pintype "bidirectional"))
      (node (ref "J4") (pin "1") (pinfunction "6_1") (pintype "passive"))
      (node (ref "R32") (pin "1") (pinfunction "1_1") (pintype "passive"))
      (node (ref "SW_DOWN") (pin "1") (pinfunction "1_1") (pintype "bidirectional"))
      (node (ref "SW_DOWN") (pin "2") (pinfunction "2_2") (pintype "bidirectional"))
    )
    (net (code "59") (name "VBATT") (class "Default")
      (node (ref "JP12") (pin "1") (pinfunction "1_1") (pintype "passive"))
      (node (ref "R22") (pin "2") (pinfunction "2_2") (pintype "passive"))
    )
    (net (code "60") (name "VCC") (class "Default")
      (node (ref "C1") (pin "1") (pinfunction "1_1") (pintype "passive"))
      (node (ref "C13") (pin "1") (pinfunction "1_1") (pintype "passive"))
      (node (ref "C14") (pin "1") (pinfunction "1_1") (pintype "passive"))
      (node (ref "C16") (pin "1") (pinfunction "1_1") (pintype "passive"))
      (node (ref "C8") (pin "1") (pinfunction "1_1") (pintype "passive"))
      (node (ref "D1") (pin "C") (pinfunction "C_C") (pintype "passive"))
      (node (ref "D7") (pin "A") (pinfunction "A_A") (pintype "passive"))
      (node (ref "IC2") (pin "4") (pinfunction "V+_4") (pintype "power_in"))
      (node (ref "IC4") (pin "9") (pinfunction "CD+_9") (pintype "passive"))
      (node (ref "J1") (pin "5") (pinfunction "5_5") (pintype "passive"))
      (node (ref "JP2") (pin "1") (pinfunction "1_1") (pintype "passive"))
      (node (ref "R10") (pin "2") (pinfunction "2_2") (pintype "passive"))
      (node (ref "R11") (pin "2") (pinfunction "2_2") (pintype "passive"))
      (node (ref "R12") (pin "2") (pinfunction "2_2") (pintype "passive"))
      (node (ref "R13") (pin "2") (pinfunction "2_2") (pintype "passive"))
      (node (ref "R14") (pin "2") (pinfunction "2_2") (pintype "passive"))
      (node (ref "R15") (pin "2") (pinfunction "2_2") (pintype "passive"))
      (node (ref "R16") (pin "2") (pinfunction "2_2") (pintype "passive"))
      (node (ref "R17") (pin "2") (pinfunction "2_2") (pintype "passive"))
      (node (ref "R18") (pin "2") (pinfunction "2_2") (pintype "passive"))
      (node (ref "R21") (pin "2") (pinfunction "2_2") (pintype "passive"))
      (node (ref "R24") (pin "2") (pinfunction "2_2") (pintype "passive"))
      (node (ref "R31") (pin "2") (pinfunction "2_2") (pintype "passive"))
      (node (ref "R32") (pin "2") (pinfunction "2_2") (pintype "passive"))
      (node (ref "R35") (pin "2") (pinfunction "2_2") (pintype "passive"))
      (node (ref "R38") (pin "1") (pinfunction "1_1") (pintype "passive"))
      (node (ref "R39") (pin "2") (pinfunction "2_2") (pintype "passive"))
      (node (ref "R42") (pin "2") (pinfunction "2_2") (pintype "passive"))
      (node (ref "R5") (pin "2") (pinfunction "2_2") (pintype "passive"))
      (node (ref "R6") (pin "2") (pinfunction "2_2") (pintype "passive"))
      (node (ref "R7") (pin "2") (pinfunction "2_2") (pintype "passive"))
      (node (ref "R8") (pin "2") (pinfunction "2_2") (pintype "passive"))
      (node (ref "R9") (pin "2") (pinfunction "2_2") (pintype "passive"))
    )
    (net (code "61") (name "unconnected-(J1-Pad1)") (class "Default")
      (node (ref "J1") (pin "1") (pinfunction "1_1") (pintype "passive"))
    )
    (net (code "62") (name "unconnected-(J1-Pad2)") (class "Default")
      (node (ref "J1") (pin "2") (pinfunction "2_2") (pintype "passive"))
    )
    (net (code "63") (name "unconnected-(J1-Pad3)") (class "Default")
      (node (ref "J1") (pin "3") (pinfunction "3_3") (pintype "passive"))
    )
    (net (code "64") (name "unconnected-(J1-Pad4)") (class "Default")
      (node (ref "J1") (pin "4") (pinfunction "4_4") (pintype "passive"))
    )
    (net (code "65") (name "unconnected-(J2-Pad1)") (class "Default")
      (node (ref "J2") (pin "1") (pinfunction "1_1") (pintype "passive"))
    )
    (net (code "66") (name "unconnected-(J2-Pad2)") (class "Default")
      (node (ref "J2") (pin "2") (pinfunction "2_2") (pintype "passive"))
    )
    (net (code "67") (name "unconnected-(J2-Pad3)") (class "Default")
      (node (ref "J2") (pin "3") (pinfunction "3_3") (pintype "passive"))
    )
    (net (code "68") (name "unconnected-(J3-Pad5)") (class "Default")
      (node (ref "J3") (pin "5") (pinfunction "5_5") (pintype "passive"))
    )
    (net (code "69") (name "unconnected-(J3-Pad6)") (class "Default")
      (node (ref "J3") (pin "6") (pinfunction "6_6") (pintype "passive"))
    )
    (net (code "70") (name "unconnected-(J3-Pad8)") (class "Default")
      (node (ref "J3") (pin "8") (pinfunction "8_8") (pintype "passive"))
    )
    (net (code "71") (name "unconnected-(J3-Pad9)") (class "Default")
      (node (ref "J3") (pin "9") (pinfunction "9_9") (pintype "passive"))
    )
    (net (code "72") (name "unconnected-(J3-Pad10)") (class "Default")
      (node (ref "J3") (pin "10") (pinfunction "10_10") (pintype "passive"))
    )
    (net (code "73") (name "unconnected-(J4-3-Pad4)") (class "Default")
      (node (ref "J4") (pin "4") (pinfunction "3_4") (pintype "passive"))
    )
    (net (code "74") (name "unconnected-(JP9-Pad1)") (class "Default")
      (node (ref "JP9") (pin "1") (pinfunction "1_1") (pintype "passive"))
    )
    (net (code "75") (name "unconnected-(JP13-Pad1)") (class "Default")
      (node (ref "JP13") (pin "1") (pinfunction "1_1") (pintype "passive"))
    )
    (net (code "76") (name "unconnected-(SW_POWB-C-Pad5)") (class "Default")
      (node (ref "SW_POW") (pin "5") (pinfunction "C_5") (pintype "bidirectional"))
    )
    (net (code "77") (name "unconnected-(SW_POWB-NC-Pad4)") (class "Default")
      (node (ref "SW_POW") (pin "4") (pinfunction "NC_4") (pintype "bidirectional"))
    )
    (net (code "78") (name "unconnected-(SW_POWB-NO-Pad6)") (class "Default")
      (node (ref "SW_POW") (pin "6") (pinfunction "NO_6") (pintype "bidirectional"))
    )
  )
)
